# RGB_Schematic.net
KiCad netlist of a schematic drawn in Altium Designer
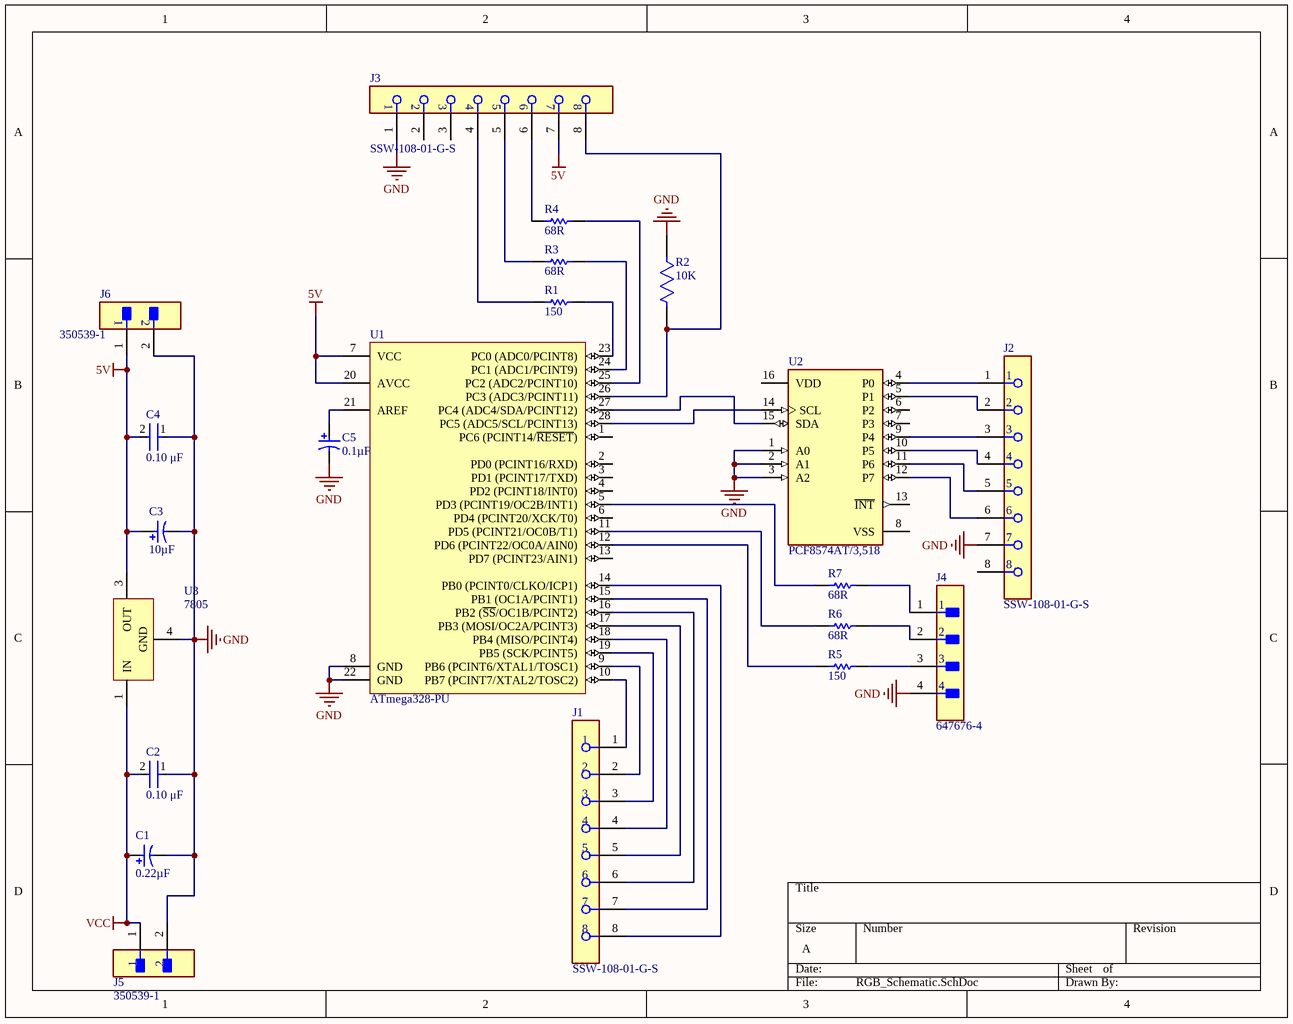
[diagram p0: RGB_Schematic.SchDoc]

(export (version "E")
  (design (tool "Eeschema 10.0.6"))
  (components
    (comp (ref "C1")
      (value "0.22µF")
      (footprint "PNSC-FP-V-D_V")
      (fields (field (name "MANUFACTURER") "Panasonic"))
      (libsource (lib "Altium Content Vault") (part "CAP-P-2"))
    )
    (comp (ref "C2")
      (value "0.10 μF")
      (footprint "FP-C1206C-EB-MFG")
      (description "C1206 0.10 μF X7R 10.00% 100 V")
      (fields (field (name "TOLERANCE") "0.1"))
      (libsource (lib "Altium Content Vault") (part "b4654b650e69147ec39a6b967a45e02"))
    )
    (comp (ref "C3")
      (value "10µF")
      (footprint "PNSC-FP-V-D_V")
      (fields (field (name "MANUFACTURER") "Panasonic"))
      (libsource (lib "Altium Content Vault") (part "CAP-P-2"))
    )
    (comp (ref "C4")
      (value "0.10 μF")
      (footprint "FP-C1206C-EB-MFG")
      (description "C1206 0.10 μF X7R 10.00% 100 V")
      (fields (field (name "TOLERANCE") "0.1"))
      (libsource (lib "Altium Content Vault") (part "b4654b650e69147ec39a6b967a45e02"))
    )
    (comp (ref "C5")
      (value "0.1µF")
      (footprint "PNSC-FP-V-D_V")
      (fields (field (name "MANUFACTURER") "Panasonic"))
      (libsource (lib "Altium Content Vault") (part "CAP-P-2"))
    )
    (comp (ref "J1")
      (value "SSW-108-01-G-S")
      (footprint "FP-SSW-108-01-G-S-MFG")
      (description "CONN RCPT 8POS 0.1 GOLD PCB")
      (libsource (lib "") (part "a32a9c29f5c2290c50060dfb8ad7212_1"))
    )
    (comp (ref "J2")
      (value "SSW-108-01-G-S")
      (footprint "FP-SSW-108-01-G-S-MFG")
      (description "CONN RCPT 8POS 0.1 GOLD PCB")
      (libsource (lib "") (part "a32a9c29f5c2290c50060dfb8ad7212_2"))
    )
    (comp (ref "J3")
      (value "SSW-108-01-G-S")
      (footprint "FP-SSW-108-01-G-S-MFG")
      (description "CONN RCPT 8POS 0.1 GOLD PCB")
      (libsource (lib "Altium Content Vault") (part "a32a9c29f5c2290c50060dfb8ad7212"))
    )
    (comp (ref "J4")
      (value "647676-4")
      (footprint "FP-647676-4-MFG")
      (description "4 Position Single Row 3.96 mm Right Angle Header Unshrouded Male Pin Connector")
      (fields (field (name "OCTOPART") "https://octopart.com/647676-4-te+connectivity-41901901"))
      (libsource (lib "Altium Content Vault") (part "299a8cea1bdcbc3624fe62c390fa72c"))
    )
    (comp (ref "J5")
      (value "350539-1")
      (footprint "FP-350539-1-MFG")
      (description "CONN HEADER VERT 2POS 5.08MM")
      (fields
        (field (name "MANUFACTURER") "TE Connectivity")
        (field (name "OCTOPART") "https://octopart.com/350539-1-te+connectivity-46510628")
      )
      (libsource (lib "Altium Content Vault") (part "3bc925449376181038e59eaffc5286c"))
    )
    (comp (ref "J6")
      (value "350539-1")
      (footprint "FP-350539-1-MFG")
      (description "CONN HEADER VERT 2POS 5.08MM")
      (fields
        (field (name "MANUFACTURER") "TE Connectivity")
        (field (name "OCTOPART") "https://octopart.com/350539-1-te+connectivity-46510628")
      )
      (libsource (lib "") (part "3bc925449376181038e59eaffc5286c_1"))
    )
    (comp (ref "R1")
      (value "150")
      (footprint "RESC3126X60X50ML10T20")
      (description "RC1210JR-07150RL")
      (fields (field (name "MANUFACTURER") "Yageo"))
      (libsource (lib "Altium Content Vault") (part "RES"))
    )
    (comp (ref "R2")
      (value "10K")
      (footprint "FP-MCS0402-IPC_A")
      (description "RES SMD 10K OHM 0.1% 1/10W 0402, MCS0402MD1002BE100")
      (fields (field (name "TOLERANCE") "0.1%"))
      (libsource (lib "Altium Content Vault") (part "1029c3af85768c4190bb7ad29bc67b5"))
    )
    (comp (ref "R3")
      (value "68R")
      (footprint "RESC1608X55X30LL20T20")
      (description "ERA3AEB680V")
      (fields (field (name "MANUFACTURER") "Panasonic"))
      (libsource (lib "Altium Content Vault") (part "RES"))
    )
    (comp (ref "R4")
      (value "68R")
      (footprint "RESC1608X55X30LL20T20")
      (description "ERA3AEB680V")
      (fields (field (name "MANUFACTURER") "Panasonic"))
      (libsource (lib "Altium Content Vault") (part "RES"))
    )
    (comp (ref "R5")
      (value "150")
      (footprint "RESC3126X60X50ML10T20")
      (description "RC1210JR-07150RL")
      (fields (field (name "MANUFACTURER") "Yageo"))
      (libsource (lib "Altium Content Vault") (part "RES"))
    )
    (comp (ref "R6")
      (value "68R")
      (footprint "RESC1608X55X30LL20T20")
      (description "ERA3AEB680V")
      (fields (field (name "MANUFACTURER") "Panasonic"))
      (libsource (lib "Altium Content Vault") (part "RES"))
    )
    (comp (ref "R7")
      (value "68R")
      (footprint "RESC1608X55X30LL20T20")
      (description "ERA3AEB680V")
      (fields (field (name "MANUFACTURER") "Panasonic"))
      (libsource (lib "Altium Content Vault") (part "RES"))
    )
    (comp (ref "U1")
      (value "ATmega328-PU")
      (footprint "28P3")
      (libsource (lib "Altium Content Vault") (part "MC-8B-ATM48-IL28"))
    )
    (comp (ref "U2")
      (value "PCF8574AT/3,518")
      (footprint "FP-SOT162-1-MFG")
      (description "IC I/O EXPANDER I2C 8B 16SOIC")
      (fields
        (field (name "MANUFACTURER") "NXP Semiconductors")
        (field (name "OCTOPART") "https://octopart.com/pcf8574at%2F3%2C518-nxp+semiconductors-11541925")
      )
      (libsource (lib "Altium Content Vault") (part "f7fde53ce59de981fb0b266a4e103eb"))
    )
    (comp (ref "U3")
      (value "7805")
      (footprint "TO-263_M")
      (description "Positive Voltage Regulator, 3-Pin D2PAK, Tape and Reel, L7805CD2T-TR")
      (libsource (lib "Altium Content Vault") (part "PM-REG-L4940-SOT3"))
    )
  )
  (nets
    (net (code "1") (name "5V") (class "Default")
      (node (ref "C3") (pin "1") (pinfunction "1_1") (pintype "passive"))
      (node (ref "C4") (pin "2") (pinfunction "2_2") (pintype "passive"))
      (node (ref "J3") (pin "7") (pinfunction "7_7") (pintype "passive"))
      (node (ref "J6") (pin "1") (pinfunction "1_1") (pintype "passive"))
      (node (ref "U1") (pin "20") (pinfunction "AVCC_20") (pintype "power_in"))
      (node (ref "U1") (pin "7") (pinfunction "VCC_7") (pintype "power_in"))
      (node (ref "U3") (pin "3") (pinfunction "OUT_3") (pintype "power_in"))
    )
    (net (code "2") (name "GND") (class "Default")
      (node (ref "C1") (pin "2") (pinfunction "2_2") (pintype "passive"))
      (node (ref "C2") (pin "1") (pinfunction "1_1") (pintype "passive"))
      (node (ref "C3") (pin "2") (pinfunction "2_2") (pintype "passive"))
      (node (ref "C4") (pin "1") (pinfunction "1_1") (pintype "passive"))
      (node (ref "C5") (pin "2") (pinfunction "2_2") (pintype "passive"))
      (node (ref "J2") (pin "7") (pinfunction "7_7") (pintype "passive"))
      (node (ref "J3") (pin "1") (pinfunction "1_1") (pintype "passive"))
      (node (ref "J4") (pin "4") (pinfunction "4_4") (pintype "passive"))
      (node (ref "J5") (pin "2") (pinfunction "2_2") (pintype "passive"))
      (node (ref "J6") (pin "2") (pinfunction "2_2") (pintype "passive"))
      (node (ref "R2") (pin "1") (pinfunction "1_1") (pintype "passive"))
      (node (ref "U1") (pin "22") (pinfunction "GND_22") (pintype "power_in"))
      (node (ref "U1") (pin "8") (pinfunction "GND_8") (pintype "power_in"))
      (node (ref "U2") (pin "1") (pinfunction "A0_1") (pintype "input"))
      (node (ref "U2") (pin "2") (pinfunction "A1_2") (pintype "input"))
      (node (ref "U2") (pin "3") (pinfunction "A2_3") (pintype "input"))
      (node (ref "U3") (pin "4") (pinfunction "GND_4") (pintype "power_in"))
    )
    (net (code "3") (name "Net-(J3-Pad4)") (class "Default")
      (node (ref "J3") (pin "4") (pinfunction "4_4") (pintype "passive"))
      (node (ref "R1") (pin "1") (pinfunction "1_1") (pintype "passive"))
    )
    (net (code "4") (name "Net-(J3-Pad5)") (class "Default")
      (node (ref "J3") (pin "5") (pinfunction "5_5") (pintype "passive"))
      (node (ref "R3") (pin "1") (pinfunction "1_1") (pintype "passive"))
    )
    (net (code "5") (name "Net-(J3-Pad6)") (class "Default")
      (node (ref "J3") (pin "6") (pinfunction "6_6") (pintype "passive"))
      (node (ref "R4") (pin "1") (pinfunction "1_1") (pintype "passive"))
    )
    (net (code "6") (name "Net-(J4-Pad1)") (class "Default")
      (node (ref "J4") (pin "1") (pinfunction "1_1") (pintype "passive"))
      (node (ref "R7") (pin "2") (pinfunction "2_2") (pintype "passive"))
    )
    (net (code "7") (name "Net-(J4-Pad2)") (class "Default")
      (node (ref "J4") (pin "2") (pinfunction "2_2") (pintype "passive"))
      (node (ref "R6") (pin "2") (pinfunction "2_2") (pintype "passive"))
    )
    (net (code "8") (name "Net-(J4-Pad3)") (class "Default")
      (node (ref "J4") (pin "3") (pinfunction "3_3") (pintype "passive"))
      (node (ref "R5") (pin "2") (pinfunction "2_2") (pintype "passive"))
    )
    (net (code "9") (name "Net-(U1-AREF)") (class "Default")
      (node (ref "C5") (pin "1") (pinfunction "1_1") (pintype "passive"))
      (node (ref "U1") (pin "21") (pinfunction "AREF_21") (pintype "power_in"))
    )
    (net (code "10") (name "Net-(U1-PB0_(PCINT0{slash}CLKO{slash}ICP1))") (class "Default")
      (node (ref "J1") (pin "8") (pinfunction "8_8") (pintype "passive"))
      (node (ref "U1") (pin "14") (pinfunction "PB0_(PCINT0/CLKO/ICP1)_14") (pintype "bidirectional"))
    )
    (net (code "11") (name "Net-(U1-PB1_(OC1A{slash}PCINT1))") (class "Default")
      (node (ref "J1") (pin "7") (pinfunction "7_7") (pintype "passive"))
      (node (ref "U1") (pin "15") (pinfunction "PB1_(OC1A/PCINT1)_15") (pintype "bidirectional"))
    )
    (net (code "12") (name "Net-(U1-PB2_(~{SS}{slash}OC1B{slash}PCINT2))") (class "Default")
      (node (ref "J1") (pin "6") (pinfunction "6_6") (pintype "passive"))
      (node (ref "U1") (pin "16") (pinfunction "PB2_(~{SS}/OC1B/PCINT2)_16") (pintype "bidirectional"))
    )
    (net (code "13") (name "Net-(U1-PB3_(MOSI{slash}OC2A{slash}PCINT3))") (class "Default")
      (node (ref "J1") (pin "5") (pinfunction "5_5") (pintype "passive"))
      (node (ref "U1") (pin "17") (pinfunction "PB3_(MOSI/OC2A/PCINT3)_17") (pintype "bidirectional"))
    )
    (net (code "14") (name "Net-(U1-PB4_(MISO{slash}PCINT4))") (class "Default")
      (node (ref "J1") (pin "4") (pinfunction "4_4") (pintype "passive"))
      (node (ref "U1") (pin "18") (pinfunction "PB4_(MISO/PCINT4)_18") (pintype "bidirectional"))
    )
    (net (code "15") (name "Net-(U1-PB5_(SCK{slash}PCINT5))") (class "Default")
      (node (ref "J1") (pin "3") (pinfunction "3_3") (pintype "passive"))
      (node (ref "U1") (pin "19") (pinfunction "PB5_(SCK/PCINT5)_19") (pintype "bidirectional"))
    )
    (net (code "16") (name "Net-(U1-PB6_(PCINT6{slash}XTAL1{slash}TOSC1))") (class "Default")
      (node (ref "J1") (pin "2") (pinfunction "2_2") (pintype "passive"))
      (node (ref "U1") (pin "9") (pinfunction "PB6_(PCINT6/XTAL1/TOSC1)_9") (pintype "bidirectional"))
    )
    (net (code "17") (name "Net-(U1-PB7_(PCINT7{slash}XTAL2{slash}TOSC2))") (class "Default")
      (node (ref "J1") (pin "1") (pinfunction "1_1") (pintype "passive"))
      (node (ref "U1") (pin "10") (pinfunction "PB7_(PCINT7/XTAL2/TOSC2)_10") (pintype "bidirectional"))
    )
    (net (code "18") (name "Net-(U1-PC0_(ADC0{slash}PCINT8))") (class "Default")
      (node (ref "R1") (pin "2") (pinfunction "2_2") (pintype "passive"))
      (node (ref "U1") (pin "23") (pinfunction "PC0_(ADC0/PCINT8)_23") (pintype "bidirectional"))
    )
    (net (code "19") (name "Net-(U1-PC1_(ADC1{slash}PCINT9))") (class "Default")
      (node (ref "R3") (pin "2") (pinfunction "2_2") (pintype "passive"))
      (node (ref "U1") (pin "24") (pinfunction "PC1_(ADC1/PCINT9)_24") (pintype "bidirectional"))
    )
    (net (code "20") (name "Net-(U1-PC2_(ADC2{slash}PCINT10))") (class "Default")
      (node (ref "R4") (pin "2") (pinfunction "2_2") (pintype "passive"))
      (node (ref "U1") (pin "25") (pinfunction "PC2_(ADC2/PCINT10)_25") (pintype "bidirectional"))
    )
    (net (code "21") (name "Net-(U1-PC3_(ADC3{slash}PCINT11))") (class "Default")
      (node (ref "J3") (pin "8") (pinfunction "8_8") (pintype "passive"))
      (node (ref "R2") (pin "2") (pinfunction "2_2") (pintype "passive"))
      (node (ref "U1") (pin "26") (pinfunction "PC3_(ADC3/PCINT11)_26") (pintype "bidirectional"))
    )
    (net (code "22") (name "Net-(U1-PC4_(ADC4{slash}SDA{slash}PCINT12))") (class "Default")
      (node (ref "U1") (pin "27") (pinfunction "PC4_(ADC4/SDA/PCINT12)_27") (pintype "bidirectional"))
      (node (ref "U2") (pin "15") (pinfunction "SDA_15") (pintype "bidirectional"))
    )
    (net (code "23") (name "Net-(U1-PC5_(ADC5{slash}SCL{slash}PCINT13))") (class "Default")
      (node (ref "U1") (pin "28") (pinfunction "PC5_(ADC5/SCL/PCINT13)_28") (pintype "bidirectional"))
      (node (ref "U2") (pin "14") (pinfunction "SCL_14") (pintype "input"))
    )
    (net (code "24") (name "Net-(U1-PD3_(PCINT19{slash}OC2B{slash}INT1))") (class "Default")
      (node (ref "R7") (pin "1") (pinfunction "1_1") (pintype "passive"))
      (node (ref "U1") (pin "5") (pinfunction "PD3_(PCINT19/OC2B/INT1)_5") (pintype "bidirectional"))
    )
    (net (code "25") (name "Net-(U1-PD5_(PCINT21{slash}OC0B{slash}T1))") (class "Default")
      (node (ref "R6") (pin "1") (pinfunction "1_1") (pintype "passive"))
      (node (ref "U1") (pin "11") (pinfunction "PD5_(PCINT21/OC0B/T1)_11") (pintype "bidirectional"))
    )
    (net (code "26") (name "Net-(U1-PD6_(PCINT22{slash}OC0A{slash}AIN0))") (class "Default")
      (node (ref "R5") (pin "1") (pinfunction "1_1") (pintype "passive"))
      (node (ref "U1") (pin "12") (pinfunction "PD6_(PCINT22/OC0A/AIN0)_12") (pintype "bidirectional"))
    )
    (net (code "27") (name "Net-(U2-P0)") (class "Default")
      (node (ref "J2") (pin "1") (pinfunction "1_1") (pintype "passive"))
      (node (ref "U2") (pin "4") (pinfunction "P0_4") (pintype "bidirectional"))
    )
    (net (code "28") (name "Net-(U2-P1)") (class "Default")
      (node (ref "J2") (pin "2") (pinfunction "2_2") (pintype "passive"))
      (node (ref "U2") (pin "5") (pinfunction "P1_5") (pintype "bidirectional"))
    )
    (net (code "29") (name "Net-(U2-P4)") (class "Default")
      (node (ref "J2") (pin "3") (pinfunction "3_3") (pintype "passive"))
      (node (ref "U2") (pin "9") (pinfunction "P4_9") (pintype "bidirectional"))
    )
    (net (code "30") (name "Net-(U2-P5)") (class "Default")
      (node (ref "J2") (pin "4") (pinfunction "4_4") (pintype "passive"))
      (node (ref "U2") (pin "10") (pinfunction "P5_10") (pintype "bidirectional"))
    )
    (net (code "31") (name "Net-(U2-P6)") (class "Default")
      (node (ref "J2") (pin "5") (pinfunction "5_5") (pintype "passive"))
      (node (ref "U2") (pin "11") (pinfunction "P6_11") (pintype "bidirectional"))
    )
    (net (code "32") (name "Net-(U2-P7)") (class "Default")
      (node (ref "J2") (pin "6") (pinfunction "6_6") (pintype "passive"))
      (node (ref "U2") (pin "12") (pinfunction "P7_12") (pintype "bidirectional"))
    )
    (net (code "33") (name "VCC") (class "Default")
      (node (ref "C1") (pin "1") (pinfunction "1_1") (pintype "passive"))
      (node (ref "C2") (pin "2") (pinfunction "2_2") (pintype "passive"))
      (node (ref "J5") (pin "1") (pinfunction "1_1") (pintype "passive"))
      (node (ref "U3") (pin "1") (pinfunction "IN_1") (pintype "power_in"))
    )
    (net (code "34") (name "unconnected-(J2-Pad8)") (class "Default")
      (node (ref "J2") (pin "8") (pinfunction "8_8") (pintype "passive"))
    )
    (net (code "35") (name "unconnected-(J3-Pad2)") (class "Default")
      (node (ref "J3") (pin "2") (pinfunction "2_2") (pintype "passive"))
    )
    (net (code "36") (name "unconnected-(J3-Pad3)") (class "Default")
      (node (ref "J3") (pin "3") (pinfunction "3_3") (pintype "passive"))
    )
    (net (code "37") (name "unconnected-(U1-PC6_(PCINT14{slash}~{RESET})-Pad1)") (class "Default")
      (node (ref "U1") (pin "1") (pinfunction "PC6_(PCINT14/~{RESET})_1") (pintype "bidirectional"))
    )
    (net (code "38") (name "unconnected-(U1-PD0_(PCINT16{slash}RXD)-Pad2)") (class "Default")
      (node (ref "U1") (pin "2") (pinfunction "PD0_(PCINT16/RXD)_2") (pintype "bidirectional"))
    )
    (net (code "39") (name "unconnected-(U1-PD1_(PCINT17{slash}TXD)-Pad3)") (class "Default")
      (node (ref "U1") (pin "3") (pinfunction "PD1_(PCINT17/TXD)_3") (pintype "bidirectional"))
    )
    (net (code "40") (name "unconnected-(U1-PD2_(PCINT18{slash}INT0)-Pad4)") (class "Default")
      (node (ref "U1") (pin "4") (pinfunction "PD2_(PCINT18/INT0)_4") (pintype "bidirectional"))
    )
    (net (code "41") (name "unconnected-(U1-PD4_(PCINT20{slash}XCK{slash}T0)-Pad6)") (class "Default")
      (node (ref "U1") (pin "6") (pinfunction "PD4_(PCINT20/XCK/T0)_6") (pintype "bidirectional"))
    )
    (net (code "42") (name "unconnected-(U1-PD7_(PCINT23{slash}AIN1)-Pad13)") (class "Default")
      (node (ref "U1") (pin "13") (pinfunction "PD7_(PCINT23/AIN1)_13") (pintype "bidirectional"))
    )
    (net (code "43") (name "unconnected-(U2-P2-Pad6)") (class "Default")
      (node (ref "U2") (pin "6") (pinfunction "P2_6") (pintype "bidirectional"))
    )
    (net (code "44") (name "unconnected-(U2-P3-Pad7)") (class "Default")
      (node (ref "U2") (pin "7") (pinfunction "P3_7") (pintype "bidirectional"))
    )
    (net (code "45") (name "unconnected-(U2-VDD-Pad16)") (class "Default")
      (node (ref "U2") (pin "16") (pinfunction "VDD_16") (pintype "power_in"))
    )
    (net (code "46") (name "unconnected-(U2-VSS-Pad8)") (class "Default")
      (node (ref "U2") (pin "8") (pinfunction "VSS_8") (pintype "power_in"))
    )
    (net (code "47") (name "unconnected-(U2-~{INT}-Pad13)") (class "Default")
      (node (ref "U2") (pin "13") (pinfunction "~{INT}_13") (pintype "output"))
    )
  )
)
